# VRAM_SIMM_MT42C8255DJ_v1_0_Sch_EasyEDA.net
KiCad netlist of a schematic drawn in EasyEDA
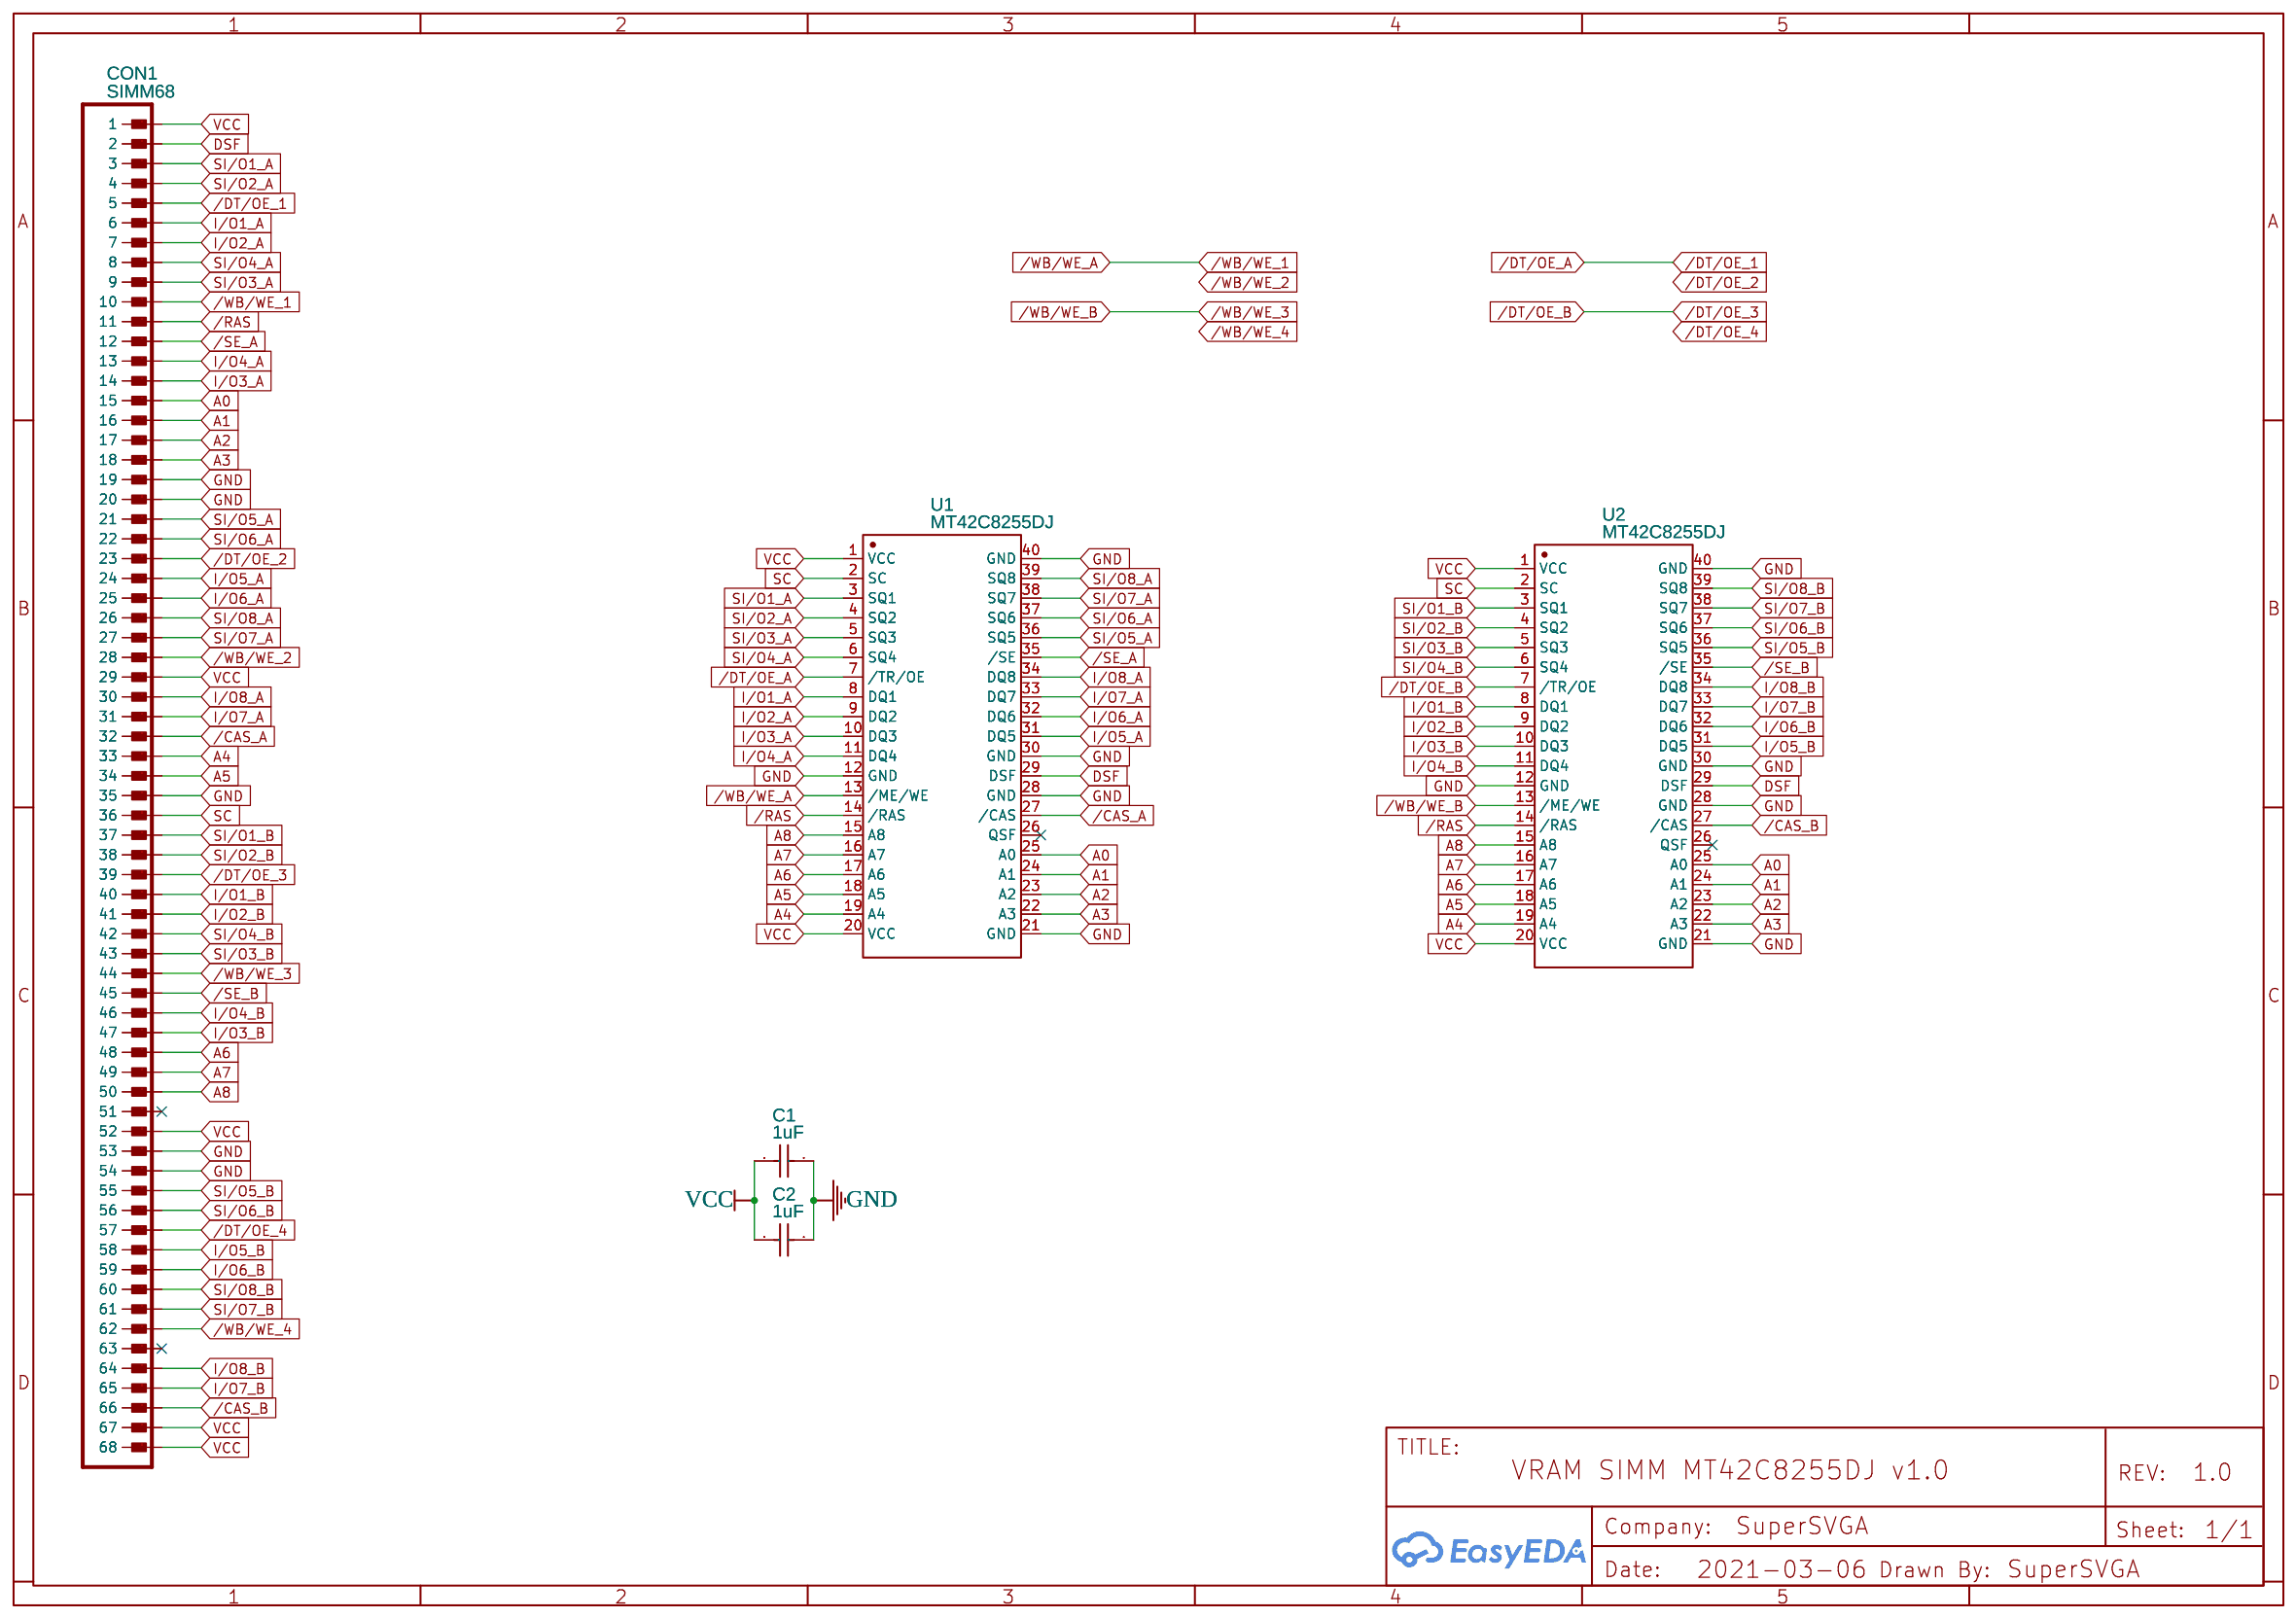
[diagram p0: schematic sheet]

(export (version "E")
  (design (tool "Eeschema 10.0.6"))
  (components
    (comp (ref "C1")
      (value "1uF")
      (fields
        (field (name "BOM_Manufacturer Part") "CL10A105KP8NNNC")
        (field (name "BOM_Supplier Part") "C26413")
      )
      (libsource (lib "") (part "CL10A105KP8NNNC"))
    )
    (comp (ref "C2")
      (value "1uF")
      (fields
        (field (name "BOM_Manufacturer Part") "CL10A105KP8NNNC")
        (field (name "BOM_Supplier Part") "C26413")
      )
      (libsource (lib "") (part "CL10A105KP8NNNC"))
    )
    (comp (ref "CON1") (value "SIMM68") (libsource (lib "") (part "SIMM68")))
    (comp (ref "U1") (value "MT42C8255DJ") (libsource (lib "") (part "MT42C8255DJ")))
    (comp (ref "U2") (value "MT42C8255DJ") (libsource (lib "") (part "MT42C8255DJ")))
  )
  (nets
    (net (code "1") (name "A0") (class "Default")
      (node (ref "CON1") (pin "15") (pinfunction "15_15") (pintype "unspecified"))
      (node (ref "U1") (pin "25") (pinfunction "A0_25") (pintype "input"))
      (node (ref "U2") (pin "25") (pinfunction "A0_25") (pintype "input"))
    )
    (net (code "2") (name "A1") (class "Default")
      (node (ref "CON1") (pin "16") (pinfunction "16_16") (pintype "unspecified"))
      (node (ref "U1") (pin "24") (pinfunction "A1_24") (pintype "input"))
      (node (ref "U2") (pin "24") (pinfunction "A1_24") (pintype "input"))
    )
    (net (code "3") (name "A2") (class "Default")
      (node (ref "CON1") (pin "17") (pinfunction "17_17") (pintype "unspecified"))
      (node (ref "U1") (pin "23") (pinfunction "A2_23") (pintype "input"))
      (node (ref "U2") (pin "23") (pinfunction "A2_23") (pintype "input"))
    )
    (net (code "4") (name "A3") (class "Default")
      (node (ref "CON1") (pin "18") (pinfunction "18_18") (pintype "unspecified"))
      (node (ref "U1") (pin "22") (pinfunction "A3_22") (pintype "input"))
      (node (ref "U2") (pin "22") (pinfunction "A3_22") (pintype "input"))
    )
    (net (code "5") (name "A4") (class "Default")
      (node (ref "CON1") (pin "33") (pinfunction "33_33") (pintype "unspecified"))
      (node (ref "U1") (pin "19") (pinfunction "A4_19") (pintype "input"))
      (node (ref "U2") (pin "19") (pinfunction "A4_19") (pintype "input"))
    )
    (net (code "6") (name "A5") (class "Default")
      (node (ref "CON1") (pin "34") (pinfunction "34_34") (pintype "unspecified"))
      (node (ref "U1") (pin "18") (pinfunction "A5_18") (pintype "input"))
      (node (ref "U2") (pin "18") (pinfunction "A5_18") (pintype "input"))
    )
    (net (code "7") (name "A6") (class "Default")
      (node (ref "CON1") (pin "48") (pinfunction "48_48") (pintype "unspecified"))
      (node (ref "U1") (pin "17") (pinfunction "A6_17") (pintype "input"))
      (node (ref "U2") (pin "17") (pinfunction "A6_17") (pintype "input"))
    )
    (net (code "8") (name "A7") (class "Default")
      (node (ref "CON1") (pin "49") (pinfunction "49_49") (pintype "unspecified"))
      (node (ref "U1") (pin "16") (pinfunction "A7_16") (pintype "input"))
      (node (ref "U2") (pin "16") (pinfunction "A7_16") (pintype "input"))
    )
    (net (code "9") (name "A8") (class "Default")
      (node (ref "CON1") (pin "50") (pinfunction "50_50") (pintype "unspecified"))
      (node (ref "U1") (pin "15") (pinfunction "A8_15") (pintype "input"))
      (node (ref "U2") (pin "15") (pinfunction "A8_15") (pintype "input"))
    )
    (net (code "10") (name "DSF") (class "Default")
      (node (ref "CON1") (pin "2") (pinfunction "2_2") (pintype "unspecified"))
      (node (ref "U1") (pin "29") (pinfunction "DSF_29") (pintype "input"))
      (node (ref "U2") (pin "29") (pinfunction "DSF_29") (pintype "input"))
    )
    (net (code "11") (name "GND") (class "Default")
      (node (ref "C1") (pin "2") (pinfunction "2_2") (pintype "input"))
      (node (ref "C2") (pin "2") (pinfunction "2_2") (pintype "input"))
      (node (ref "CON1") (pin "19") (pinfunction "19_19") (pintype "unspecified"))
      (node (ref "CON1") (pin "20") (pinfunction "20_20") (pintype "unspecified"))
      (node (ref "CON1") (pin "35") (pinfunction "35_35") (pintype "unspecified"))
      (node (ref "CON1") (pin "53") (pinfunction "53_53") (pintype "unspecified"))
      (node (ref "CON1") (pin "54") (pinfunction "54_54") (pintype "unspecified"))
      (node (ref "U1") (pin "12") (pinfunction "GND_12") (pintype "passive"))
      (node (ref "U1") (pin "21") (pinfunction "GND_21") (pintype "passive"))
      (node (ref "U1") (pin "28") (pinfunction "GND_28") (pintype "input"))
      (node (ref "U1") (pin "30") (pinfunction "GND_30") (pintype "passive"))
      (node (ref "U1") (pin "40") (pinfunction "GND_40") (pintype "passive"))
      (node (ref "U2") (pin "12") (pinfunction "GND_12") (pintype "passive"))
      (node (ref "U2") (pin "21") (pinfunction "GND_21") (pintype "passive"))
      (node (ref "U2") (pin "28") (pinfunction "GND_28") (pintype "input"))
      (node (ref "U2") (pin "30") (pinfunction "GND_30") (pintype "passive"))
      (node (ref "U2") (pin "40") (pinfunction "GND_40") (pintype "passive"))
    )
    (net (code "12") (name "I{slash}O1_A") (class "Default")
      (node (ref "CON1") (pin "6") (pinfunction "6_6") (pintype "unspecified"))
      (node (ref "U1") (pin "8") (pinfunction "DQ1_8") (pintype "bidirectional"))
    )
    (net (code "13") (name "I{slash}O1_B") (class "Default")
      (node (ref "CON1") (pin "40") (pinfunction "40_40") (pintype "unspecified"))
      (node (ref "U2") (pin "8") (pinfunction "DQ1_8") (pintype "bidirectional"))
    )
    (net (code "14") (name "I{slash}O2_A") (class "Default")
      (node (ref "CON1") (pin "7") (pinfunction "7_7") (pintype "unspecified"))
      (node (ref "U1") (pin "9") (pinfunction "DQ2_9") (pintype "bidirectional"))
    )
    (net (code "15") (name "I{slash}O2_B") (class "Default")
      (node (ref "CON1") (pin "41") (pinfunction "41_41") (pintype "unspecified"))
      (node (ref "U2") (pin "9") (pinfunction "DQ2_9") (pintype "bidirectional"))
    )
    (net (code "16") (name "I{slash}O3_A") (class "Default")
      (node (ref "CON1") (pin "14") (pinfunction "14_14") (pintype "unspecified"))
      (node (ref "U1") (pin "10") (pinfunction "DQ3_10") (pintype "bidirectional"))
    )
    (net (code "17") (name "I{slash}O3_B") (class "Default")
      (node (ref "CON1") (pin "47") (pinfunction "47_47") (pintype "unspecified"))
      (node (ref "U2") (pin "10") (pinfunction "DQ3_10") (pintype "bidirectional"))
    )
    (net (code "18") (name "I{slash}O4_A") (class "Default")
      (node (ref "CON1") (pin "13") (pinfunction "13_13") (pintype "unspecified"))
      (node (ref "U1") (pin "11") (pinfunction "DQ4_11") (pintype "bidirectional"))
    )
    (net (code "19") (name "I{slash}O4_B") (class "Default")
      (node (ref "CON1") (pin "46") (pinfunction "46_46") (pintype "unspecified"))
      (node (ref "U2") (pin "11") (pinfunction "DQ4_11") (pintype "bidirectional"))
    )
    (net (code "20") (name "I{slash}O5_A") (class "Default")
      (node (ref "CON1") (pin "24") (pinfunction "24_24") (pintype "unspecified"))
      (node (ref "U1") (pin "31") (pinfunction "DQ5_31") (pintype "bidirectional"))
    )
    (net (code "21") (name "I{slash}O5_B") (class "Default")
      (node (ref "CON1") (pin "58") (pinfunction "58_58") (pintype "unspecified"))
      (node (ref "U2") (pin "31") (pinfunction "DQ5_31") (pintype "bidirectional"))
    )
    (net (code "22") (name "I{slash}O6_A") (class "Default")
      (node (ref "CON1") (pin "25") (pinfunction "25_25") (pintype "unspecified"))
      (node (ref "U1") (pin "32") (pinfunction "DQ6_32") (pintype "bidirectional"))
    )
    (net (code "23") (name "I{slash}O6_B") (class "Default")
      (node (ref "CON1") (pin "59") (pinfunction "59_59") (pintype "unspecified"))
      (node (ref "U2") (pin "32") (pinfunction "DQ6_32") (pintype "bidirectional"))
    )
    (net (code "24") (name "I{slash}O7_A") (class "Default")
      (node (ref "CON1") (pin "31") (pinfunction "31_31") (pintype "unspecified"))
      (node (ref "U1") (pin "33") (pinfunction "DQ7_33") (pintype "bidirectional"))
    )
    (net (code "25") (name "I{slash}O7_B") (class "Default")
      (node (ref "CON1") (pin "65") (pinfunction "65_65") (pintype "unspecified"))
      (node (ref "U2") (pin "33") (pinfunction "DQ7_33") (pintype "bidirectional"))
    )
    (net (code "26") (name "I{slash}O8_A") (class "Default")
      (node (ref "CON1") (pin "30") (pinfunction "30_30") (pintype "unspecified"))
      (node (ref "U1") (pin "34") (pinfunction "DQ8_34") (pintype "bidirectional"))
    )
    (net (code "27") (name "I{slash}O8_B") (class "Default")
      (node (ref "CON1") (pin "64") (pinfunction "64_64") (pintype "unspecified"))
      (node (ref "U2") (pin "34") (pinfunction "DQ8_34") (pintype "bidirectional"))
    )
    (net (code "28") (name "SC") (class "Default")
      (node (ref "CON1") (pin "36") (pinfunction "36_36") (pintype "unspecified"))
      (node (ref "U1") (pin "2") (pinfunction "SC_2") (pintype "input"))
      (node (ref "U2") (pin "2") (pinfunction "SC_2") (pintype "input"))
    )
    (net (code "29") (name "SI{slash}O1_A") (class "Default")
      (node (ref "CON1") (pin "3") (pinfunction "3_3") (pintype "unspecified"))
      (node (ref "U1") (pin "3") (pinfunction "SQ1_3") (pintype "bidirectional"))
    )
    (net (code "30") (name "SI{slash}O1_B") (class "Default")
      (node (ref "CON1") (pin "37") (pinfunction "37_37") (pintype "unspecified"))
      (node (ref "U2") (pin "3") (pinfunction "SQ1_3") (pintype "bidirectional"))
    )
    (net (code "31") (name "SI{slash}O2_A") (class "Default")
      (node (ref "CON1") (pin "4") (pinfunction "4_4") (pintype "unspecified"))
      (node (ref "U1") (pin "4") (pinfunction "SQ2_4") (pintype "bidirectional"))
    )
    (net (code "32") (name "SI{slash}O2_B") (class "Default")
      (node (ref "CON1") (pin "38") (pinfunction "38_38") (pintype "unspecified"))
      (node (ref "U2") (pin "4") (pinfunction "SQ2_4") (pintype "bidirectional"))
    )
    (net (code "33") (name "SI{slash}O3_A") (class "Default")
      (node (ref "CON1") (pin "9") (pinfunction "9_9") (pintype "unspecified"))
      (node (ref "U1") (pin "5") (pinfunction "SQ3_5") (pintype "bidirectional"))
    )
    (net (code "34") (name "SI{slash}O3_B") (class "Default")
      (node (ref "CON1") (pin "43") (pinfunction "43_43") (pintype "unspecified"))
      (node (ref "U2") (pin "5") (pinfunction "SQ3_5") (pintype "bidirectional"))
    )
    (net (code "35") (name "SI{slash}O4_A") (class "Default")
      (node (ref "CON1") (pin "8") (pinfunction "8_8") (pintype "unspecified"))
      (node (ref "U1") (pin "6") (pinfunction "SQ4_6") (pintype "bidirectional"))
    )
    (net (code "36") (name "SI{slash}O4_B") (class "Default")
      (node (ref "CON1") (pin "42") (pinfunction "42_42") (pintype "unspecified"))
      (node (ref "U2") (pin "6") (pinfunction "SQ4_6") (pintype "bidirectional"))
    )
    (net (code "37") (name "SI{slash}O5_A") (class "Default")
      (node (ref "CON1") (pin "21") (pinfunction "21_21") (pintype "unspecified"))
      (node (ref "U1") (pin "36") (pinfunction "SQ5_36") (pintype "bidirectional"))
    )
    (net (code "38") (name "SI{slash}O5_B") (class "Default")
      (node (ref "CON1") (pin "55") (pinfunction "55_55") (pintype "unspecified"))
      (node (ref "U2") (pin "36") (pinfunction "SQ5_36") (pintype "bidirectional"))
    )
    (net (code "39") (name "SI{slash}O6_A") (class "Default")
      (node (ref "CON1") (pin "22") (pinfunction "22_22") (pintype "unspecified"))
      (node (ref "U1") (pin "37") (pinfunction "SQ6_37") (pintype "bidirectional"))
    )
    (net (code "40") (name "SI{slash}O6_B") (class "Default")
      (node (ref "CON1") (pin "56") (pinfunction "56_56") (pintype "unspecified"))
      (node (ref "U2") (pin "37") (pinfunction "SQ6_37") (pintype "bidirectional"))
    )
    (net (code "41") (name "SI{slash}O7_A") (class "Default")
      (node (ref "CON1") (pin "27") (pinfunction "27_27") (pintype "unspecified"))
      (node (ref "U1") (pin "38") (pinfunction "SQ7_38") (pintype "bidirectional"))
    )
    (net (code "42") (name "SI{slash}O7_B") (class "Default")
      (node (ref "CON1") (pin "61") (pinfunction "61_61") (pintype "unspecified"))
      (node (ref "U2") (pin "38") (pinfunction "SQ7_38") (pintype "bidirectional"))
    )
    (net (code "43") (name "SI{slash}O8_A") (class "Default")
      (node (ref "CON1") (pin "26") (pinfunction "26_26") (pintype "unspecified"))
      (node (ref "U1") (pin "39") (pinfunction "SQ8_39") (pintype "bidirectional"))
    )
    (net (code "44") (name "SI{slash}O8_B") (class "Default")
      (node (ref "CON1") (pin "60") (pinfunction "60_60") (pintype "unspecified"))
      (node (ref "U2") (pin "39") (pinfunction "SQ8_39") (pintype "bidirectional"))
    )
    (net (code "45") (name "VCC") (class "Default")
      (node (ref "C1") (pin "1") (pinfunction "1_1") (pintype "input"))
      (node (ref "C2") (pin "1") (pinfunction "1_1") (pintype "input"))
      (node (ref "CON1") (pin "1") (pinfunction "1_1") (pintype "unspecified"))
      (node (ref "CON1") (pin "29") (pinfunction "29_29") (pintype "unspecified"))
      (node (ref "CON1") (pin "52") (pinfunction "52_52") (pintype "unspecified"))
      (node (ref "CON1") (pin "67") (pinfunction "67_67") (pintype "unspecified"))
      (node (ref "CON1") (pin "68") (pinfunction "68_68") (pintype "unspecified"))
      (node (ref "U1") (pin "1") (pinfunction "VCC_1") (pintype "passive"))
      (node (ref "U1") (pin "20") (pinfunction "VCC_20") (pintype "passive"))
      (node (ref "U2") (pin "1") (pinfunction "VCC_1") (pintype "passive"))
      (node (ref "U2") (pin "20") (pinfunction "VCC_20") (pintype "passive"))
    )
    (net (code "46") (name "unconnected-(CON1-Pad51)") (class "Default")
      (node (ref "CON1") (pin "51") (pinfunction "51_51") (pintype "unspecified+no_connect"))
    )
    (net (code "47") (name "unconnected-(CON1-Pad63)") (class "Default")
      (node (ref "CON1") (pin "63") (pinfunction "63_63") (pintype "unspecified+no_connect"))
    )
    (net (code "48") (name "unconnected-(U1-QSF-Pad26)") (class "Default")
      (node (ref "U1") (pin "26") (pinfunction "QSF_26") (pintype "input+no_connect"))
    )
    (net (code "49") (name "unconnected-(U2-QSF-Pad26)") (class "Default")
      (node (ref "U2") (pin "26") (pinfunction "QSF_26") (pintype "input+no_connect"))
    )
    (net (code "50") (name "{slash}CAS_A") (class "Default")
      (node (ref "CON1") (pin "32") (pinfunction "32_32") (pintype "unspecified"))
      (node (ref "U1") (pin "27") (pinfunction "/CAS_27") (pintype "input"))
    )
    (net (code "51") (name "{slash}CAS_B") (class "Default")
      (node (ref "CON1") (pin "66") (pinfunction "66_66") (pintype "unspecified"))
      (node (ref "U2") (pin "27") (pinfunction "/CAS_27") (pintype "input"))
    )
    (net (code "52") (name "{slash}DT{slash}OE_1") (class "Default")
      (node (ref "CON1") (pin "5") (pinfunction "5_5") (pintype "unspecified"))
      (node (ref "U1") (pin "7") (pinfunction "/TR/OE_7") (pintype "input"))
    )
    (net (code "53") (name "{slash}DT{slash}OE_2") (class "Default")
      (node (ref "CON1") (pin "23") (pinfunction "23_23") (pintype "unspecified"))
    )
    (net (code "54") (name "{slash}DT{slash}OE_3") (class "Default")
      (node (ref "CON1") (pin "39") (pinfunction "39_39") (pintype "unspecified"))
      (node (ref "U2") (pin "7") (pinfunction "/TR/OE_7") (pintype "input"))
    )
    (net (code "55") (name "{slash}DT{slash}OE_4") (class "Default")
      (node (ref "CON1") (pin "57") (pinfunction "57_57") (pintype "unspecified"))
    )
    (net (code "56") (name "{slash}RAS") (class "Default")
      (node (ref "CON1") (pin "11") (pinfunction "11_11") (pintype "unspecified"))
      (node (ref "U1") (pin "14") (pinfunction "/RAS_14") (pintype "input"))
      (node (ref "U2") (pin "14") (pinfunction "/RAS_14") (pintype "input"))
    )
    (net (code "57") (name "{slash}SE_A") (class "Default")
      (node (ref "CON1") (pin "12") (pinfunction "12_12") (pintype "unspecified"))
      (node (ref "U1") (pin "35") (pinfunction "/SE_35") (pintype "input"))
    )
    (net (code "58") (name "{slash}SE_B") (class "Default")
      (node (ref "CON1") (pin "45") (pinfunction "45_45") (pintype "unspecified"))
      (node (ref "U2") (pin "35") (pinfunction "/SE_35") (pintype "input"))
    )
    (net (code "59") (name "{slash}WB{slash}WE_1") (class "Default")
      (node (ref "CON1") (pin "10") (pinfunction "10_10") (pintype "unspecified"))
      (node (ref "U1") (pin "13") (pinfunction "/ME/WE_13") (pintype "input"))
    )
    (net (code "60") (name "{slash}WB{slash}WE_2") (class "Default")
      (node (ref "CON1") (pin "28") (pinfunction "28_28") (pintype "unspecified"))
    )
    (net (code "61") (name "{slash}WB{slash}WE_3") (class "Default")
      (node (ref "CON1") (pin "44") (pinfunction "44_44") (pintype "unspecified"))
      (node (ref "U2") (pin "13") (pinfunction "/ME/WE_13") (pintype "input"))
    )
    (net (code "62") (name "{slash}WB{slash}WE_4") (class "Default")
      (node (ref "CON1") (pin "62") (pinfunction "62_62") (pintype "unspecified"))
    )
  )
)
